# My-VONE-6502_Hex_Display_8_Data_16_Adres.net
KiCad netlist of a schematic drawn in EasyEDA
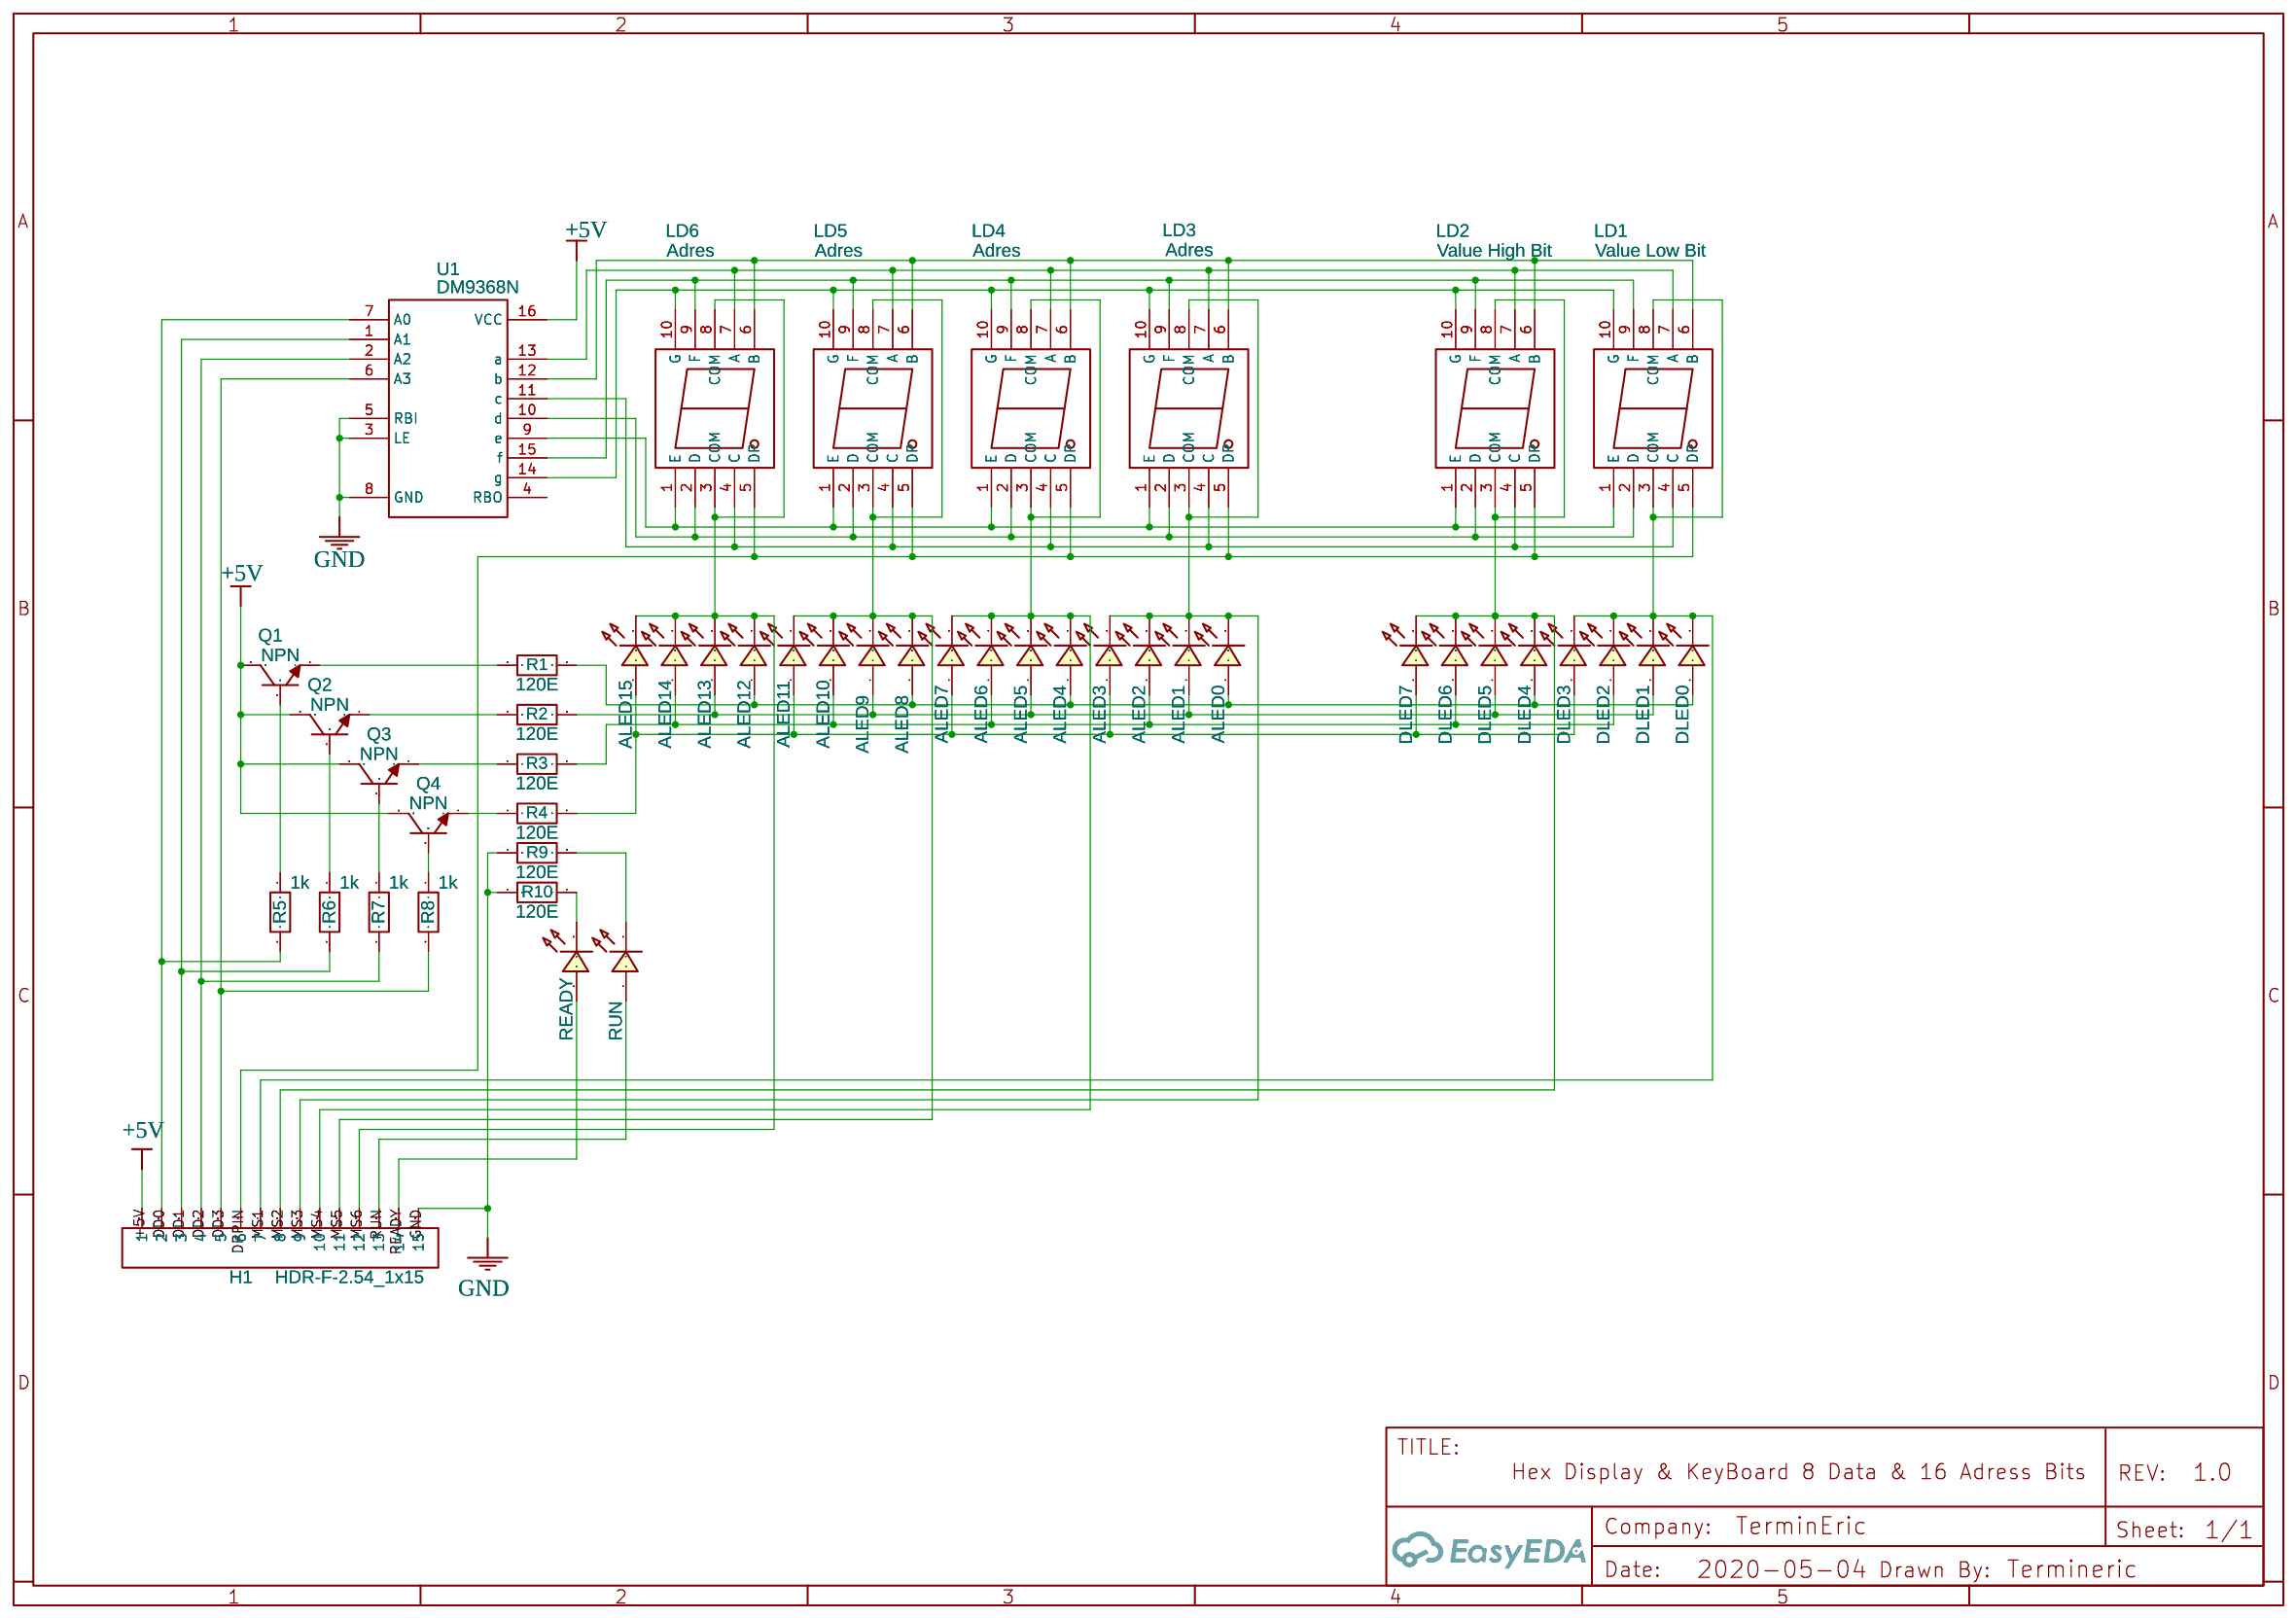
[diagram p0: schematic sheet]

(export (version "E")
  (design (tool "Eeschema 10.0.6"))
  (components
    (comp (ref "ALED0") (value "A0") (libsource (lib "") (part "LED-0603_R")))
    (comp (ref "ALED1") (value "A1") (libsource (lib "") (part "LED-0603_R")))
    (comp (ref "ALED2") (value "A2") (libsource (lib "") (part "LED-0603_R")))
    (comp (ref "ALED3") (value "A3") (libsource (lib "") (part "LED-0603_R")))
    (comp (ref "ALED4") (value "A4") (libsource (lib "") (part "LED-0603_R")))
    (comp (ref "ALED5") (value "A5") (libsource (lib "") (part "LED-0603_R")))
    (comp (ref "ALED6") (value "A6") (libsource (lib "") (part "LED-0603_R")))
    (comp (ref "ALED7") (value "A7") (libsource (lib "") (part "LED-0603_R")))
    (comp (ref "ALED8") (value "A8") (libsource (lib "") (part "LED-0603_R")))
    (comp (ref "ALED9") (value "A9") (libsource (lib "") (part "LED-0603_R")))
    (comp (ref "ALED10") (value "A10") (libsource (lib "") (part "LED-0603_R")))
    (comp (ref "ALED11") (value "A11") (libsource (lib "") (part "LED-0603_R")))
    (comp (ref "ALED12") (value "A12") (libsource (lib "") (part "LED-0603_R")))
    (comp (ref "ALED13") (value "A13") (libsource (lib "") (part "LED-0603_R")))
    (comp (ref "ALED14") (value "A14") (libsource (lib "") (part "LED-0603_R")))
    (comp (ref "ALED15") (value "A15") (libsource (lib "") (part "LED-0603_R")))
    (comp (ref "DLED0") (value "D0") (libsource (lib "") (part "LED-0603_R_1")))
    (comp (ref "DLED1") (value "D1") (libsource (lib "") (part "LED-0603_R_1")))
    (comp (ref "DLED2") (value "D2") (libsource (lib "") (part "LED-0603_R_1")))
    (comp (ref "DLED3") (value "D3") (libsource (lib "") (part "LED-0603_R_1")))
    (comp (ref "DLED4") (value "D4") (libsource (lib "") (part "LED-0603_R_1")))
    (comp (ref "DLED5") (value "D5") (libsource (lib "") (part "LED-0603_R_1")))
    (comp (ref "DLED6") (value "D6") (libsource (lib "") (part "LED-0603_R_1")))
    (comp (ref "DLED7") (value "D7") (libsource (lib "") (part "LED-0603_R_1")))
    (comp (ref "H1")
      (value "HDR-F-2.54_1x15")
      (fields (field (name "BOM_Supplier Part") "C124408"))
      (libsource (lib "") (part "HDR-F-2.54_1x15"))
    )
    (comp (ref "LD1")
      (value "Value Low Bit")
      (fields
        (field (name "BOM_Manufacturer Part") "SLR0561DBA1BD")
        (field (name "BOM_Supplier Part") "C225938")
      )
      (libsource (lib "") (part "Unknown_815_-610"))
    )
    (comp (ref "LD2")
      (value "Value High Bit")
      (fields
        (field (name "BOM_Manufacturer Part") "SLR0561DBA1BD")
        (field (name "BOM_Supplier Part") "C225938")
      )
      (libsource (lib "") (part "Unknown_735_-610"))
    )
    (comp (ref "LD3")
      (value "Adres")
      (fields
        (field (name "BOM_Manufacturer Part") "SLR0561DBA1BD")
        (field (name "BOM_Supplier Part") "SC 52-11 RT")
      )
      (libsource (lib "") (part "Unknown_580_-610"))
    )
    (comp (ref "LD4")
      (value "Adres")
      (fields
        (field (name "BOM_Manufacturer Part") "SLR0561DBA1BD")
        (field (name "BOM_Supplier Part") "C225938")
      )
      (libsource (lib "") (part "Unknown_500_-610"))
    )
    (comp (ref "LD5")
      (value "Adres")
      (fields
        (field (name "BOM_Manufacturer Part") "SLR0561DBA1BD")
        (field (name "BOM_Supplier Part") "C225938")
      )
      (libsource (lib "") (part "Unknown_420_-610"))
    )
    (comp (ref "LD6")
      (value "Adres")
      (fields
        (field (name "BOM_Manufacturer Part") "SLR0561DBA1BD")
        (field (name "BOM_Supplier Part") "C225938")
      )
      (libsource (lib "") (part "Unknown_340_-610"))
    )
    (comp (ref "Q1")
      (value "NPN")
      (fields (field (name "BOM_Manufacturer Part") "2N3904") (field (name "BOM_Supplier Part") "C118538"))
      (libsource (lib "") (part "Unknown_120_-470"))
    )
    (comp (ref "Q2")
      (value "NPN")
      (fields (field (name "BOM_Manufacturer Part") "2N3904") (field (name "BOM_Supplier Part") "C118538"))
      (libsource (lib "") (part "Unknown_145_-445"))
    )
    (comp (ref "Q3")
      (value "NPN")
      (fields (field (name "BOM_Manufacturer Part") "2N3904") (field (name "BOM_Supplier Part") "C118538"))
      (libsource (lib "") (part "Unknown_170_-420"))
    )
    (comp (ref "Q4")
      (value "NPN")
      (fields (field (name "BOM_Manufacturer Part") "2N3904") (field (name "BOM_Supplier Part") "C118538"))
      (libsource (lib "") (part "Unknown_195_-395"))
    )
    (comp (ref "R1") (value "120E") (libsource (lib "") (part "R_0201_EU")))
    (comp (ref "R2") (value "120E") (libsource (lib "") (part "R_0201_EU")))
    (comp (ref "R3") (value "120E") (libsource (lib "") (part "R_0201_EU")))
    (comp (ref "R4") (value "120E") (libsource (lib "") (part "R_0201_EU")))
    (comp (ref "R5") (value "1k") (libsource (lib "") (part "Res_AXIAL-0.3(1/8W)_EU")))
    (comp (ref "R6") (value "1k") (libsource (lib "") (part "Res_AXIAL-0.3(1/8W)_EU")))
    (comp (ref "R7") (value "1k") (libsource (lib "") (part "Res_AXIAL-0.3(1/8W)_EU")))
    (comp (ref "R8") (value "1k") (libsource (lib "") (part "Res_AXIAL-0.3(1/8W)_EU")))
    (comp (ref "R9") (value "120E") (libsource (lib "") (part "R_0201_EU")))
    (comp (ref "R10") (value "120E") (libsource (lib "") (part "R_0201_EU")))
    (comp (ref "READY") (value "A15") (libsource (lib "") (part "LED-0603_R_2")))
    (comp (ref "RUN") (value "A15") (libsource (lib "") (part "LED-0603_R_3")))
    (comp (ref "U1") (value "DM9368N") (libsource (lib "") (part "DM9368N")))
  )
  (nets
    (net (code "1") (name "+5V") (class "Default")
      (node (ref "H1") (pin "1") (pinfunction "1_1") (pintype "unspecified"))
      (node (ref "Q1") (pin "3") (pinfunction "C_3") (pintype "unspecified"))
      (node (ref "Q2") (pin "3") (pinfunction "C_3") (pintype "unspecified"))
      (node (ref "Q3") (pin "3") (pinfunction "C_3") (pintype "unspecified"))
      (node (ref "Q4") (pin "3") (pinfunction "C_3") (pintype "unspecified"))
      (node (ref "U1") (pin "16") (pinfunction "VCC_16") (pintype "passive"))
    )
    (net (code "2") (name "/DD0") (class "Default")
      (node (ref "H1") (pin "2") (pinfunction "2_2") (pintype "unspecified"))
      (node (ref "R5") (pin "2") (pinfunction "2_2") (pintype "unspecified"))
      (node (ref "U1") (pin "7") (pinfunction "A0_7") (pintype "unspecified"))
    )
    (net (code "3") (name "/DD1") (class "Default")
      (node (ref "H1") (pin "3") (pinfunction "3_3") (pintype "unspecified"))
      (node (ref "R6") (pin "2") (pinfunction "2_2") (pintype "unspecified"))
      (node (ref "U1") (pin "1") (pinfunction "A1_1") (pintype "unspecified"))
    )
    (net (code "4") (name "/DD2") (class "Default")
      (node (ref "H1") (pin "4") (pinfunction "4_4") (pintype "unspecified"))
      (node (ref "R7") (pin "2") (pinfunction "2_2") (pintype "unspecified"))
      (node (ref "U1") (pin "2") (pinfunction "A2_2") (pintype "unspecified"))
    )
    (net (code "5") (name "/DD3") (class "Default")
      (node (ref "H1") (pin "5") (pinfunction "5_5") (pintype "unspecified"))
      (node (ref "R8") (pin "2") (pinfunction "2_2") (pintype "unspecified"))
      (node (ref "U1") (pin "6") (pinfunction "A3_6") (pintype "unspecified"))
    )
    (net (code "6") (name "/DPPIN") (class "Default")
      (node (ref "H1") (pin "6") (pinfunction "6_6") (pintype "unspecified"))
      (node (ref "LD1") (pin "5") (pinfunction "DP_5") (pintype "unspecified"))
      (node (ref "LD2") (pin "5") (pinfunction "DP_5") (pintype "unspecified"))
      (node (ref "LD3") (pin "5") (pinfunction "DP_5") (pintype "unspecified"))
      (node (ref "LD4") (pin "5") (pinfunction "DP_5") (pintype "unspecified"))
      (node (ref "LD5") (pin "5") (pinfunction "DP_5") (pintype "unspecified"))
      (node (ref "LD6") (pin "5") (pinfunction "DP_5") (pintype "unspecified"))
    )
    (net (code "7") (name "/MS1") (class "Default")
      (node (ref "DLED0") (pin "2") (pinfunction "2_2") (pintype "unspecified"))
      (node (ref "DLED1") (pin "2") (pinfunction "2_2") (pintype "unspecified"))
      (node (ref "DLED2") (pin "2") (pinfunction "2_2") (pintype "unspecified"))
      (node (ref "DLED3") (pin "2") (pinfunction "2_2") (pintype "unspecified"))
      (node (ref "H1") (pin "7") (pinfunction "7_7") (pintype "unspecified"))
      (node (ref "LD1") (pin "3") (pinfunction "COM_3") (pintype "unspecified"))
      (node (ref "LD1") (pin "8") (pinfunction "COM_8") (pintype "unspecified"))
    )
    (net (code "8") (name "/MS2") (class "Default")
      (node (ref "DLED4") (pin "2") (pinfunction "2_2") (pintype "unspecified"))
      (node (ref "DLED5") (pin "2") (pinfunction "2_2") (pintype "unspecified"))
      (node (ref "DLED6") (pin "2") (pinfunction "2_2") (pintype "unspecified"))
      (node (ref "DLED7") (pin "2") (pinfunction "2_2") (pintype "unspecified"))
      (node (ref "H1") (pin "8") (pinfunction "8_8") (pintype "unspecified"))
      (node (ref "LD2") (pin "3") (pinfunction "COM_3") (pintype "unspecified"))
      (node (ref "LD2") (pin "8") (pinfunction "COM_8") (pintype "unspecified"))
    )
    (net (code "9") (name "/MS3") (class "Default")
      (node (ref "ALED0") (pin "2") (pinfunction "2_2") (pintype "unspecified"))
      (node (ref "ALED1") (pin "2") (pinfunction "2_2") (pintype "unspecified"))
      (node (ref "ALED2") (pin "2") (pinfunction "2_2") (pintype "unspecified"))
      (node (ref "ALED3") (pin "2") (pinfunction "2_2") (pintype "unspecified"))
      (node (ref "H1") (pin "9") (pinfunction "9_9") (pintype "unspecified"))
      (node (ref "LD3") (pin "3") (pinfunction "COM_3") (pintype "unspecified"))
      (node (ref "LD3") (pin "8") (pinfunction "COM_8") (pintype "unspecified"))
    )
    (net (code "10") (name "/MS4") (class "Default")
      (node (ref "ALED4") (pin "2") (pinfunction "2_2") (pintype "unspecified"))
      (node (ref "ALED5") (pin "2") (pinfunction "2_2") (pintype "unspecified"))
      (node (ref "ALED6") (pin "2") (pinfunction "2_2") (pintype "unspecified"))
      (node (ref "ALED7") (pin "2") (pinfunction "2_2") (pintype "unspecified"))
      (node (ref "H1") (pin "10") (pinfunction "10_10") (pintype "unspecified"))
      (node (ref "LD4") (pin "3") (pinfunction "COM_3") (pintype "unspecified"))
      (node (ref "LD4") (pin "8") (pinfunction "COM_8") (pintype "unspecified"))
    )
    (net (code "11") (name "/MS5") (class "Default")
      (node (ref "ALED10") (pin "2") (pinfunction "2_2") (pintype "unspecified"))
      (node (ref "ALED11") (pin "2") (pinfunction "2_2") (pintype "unspecified"))
      (node (ref "ALED8") (pin "2") (pinfunction "2_2") (pintype "unspecified"))
      (node (ref "ALED9") (pin "2") (pinfunction "2_2") (pintype "unspecified"))
      (node (ref "H1") (pin "11") (pinfunction "11_11") (pintype "unspecified"))
      (node (ref "LD5") (pin "3") (pinfunction "COM_3") (pintype "unspecified"))
      (node (ref "LD5") (pin "8") (pinfunction "COM_8") (pintype "unspecified"))
    )
    (net (code "12") (name "/MS6") (class "Default")
      (node (ref "ALED12") (pin "2") (pinfunction "2_2") (pintype "unspecified"))
      (node (ref "ALED13") (pin "2") (pinfunction "2_2") (pintype "unspecified"))
      (node (ref "ALED14") (pin "2") (pinfunction "2_2") (pintype "unspecified"))
      (node (ref "ALED15") (pin "2") (pinfunction "2_2") (pintype "unspecified"))
      (node (ref "H1") (pin "12") (pinfunction "12_12") (pintype "unspecified"))
      (node (ref "LD6") (pin "3") (pinfunction "COM_3") (pintype "unspecified"))
      (node (ref "LD6") (pin "8") (pinfunction "COM_8") (pintype "unspecified"))
    )
    (net (code "13") (name "/READY") (class "Default")
      (node (ref "H1") (pin "14") (pinfunction "14_14") (pintype "unspecified"))
      (node (ref "READY") (pin "1") (pinfunction "1_1") (pintype "unspecified"))
    )
    (net (code "14") (name "/RUN") (class "Default")
      (node (ref "H1") (pin "13") (pinfunction "13_13") (pintype "unspecified"))
      (node (ref "RUN") (pin "1") (pinfunction "1_1") (pintype "unspecified"))
    )
    (net (code "15") (name "GND") (class "Default")
      (node (ref "H1") (pin "15") (pinfunction "15_15") (pintype "unspecified"))
      (node (ref "R10") (pin "1") (pinfunction "1_1") (pintype "unspecified"))
      (node (ref "R9") (pin "1") (pinfunction "1_1") (pintype "unspecified"))
      (node (ref "U1") (pin "3") (pinfunction "LE_3") (pintype "unspecified"))
      (node (ref "U1") (pin "5") (pinfunction "RBI_5") (pintype "unspecified"))
      (node (ref "U1") (pin "8") (pinfunction "GND_8") (pintype "passive"))
    )
    (net (code "16") (name "Net-(ALED0-Pad1)") (class "Default")
      (node (ref "ALED0") (pin "1") (pinfunction "1_1") (pintype "unspecified"))
      (node (ref "ALED12") (pin "1") (pinfunction "1_1") (pintype "unspecified"))
      (node (ref "ALED4") (pin "1") (pinfunction "1_1") (pintype "unspecified"))
      (node (ref "ALED8") (pin "1") (pinfunction "1_1") (pintype "unspecified"))
      (node (ref "DLED0") (pin "1") (pinfunction "1_1") (pintype "unspecified"))
      (node (ref "DLED4") (pin "1") (pinfunction "1_1") (pintype "unspecified"))
      (node (ref "R1") (pin "2") (pinfunction "2_2") (pintype "unspecified"))
    )
    (net (code "17") (name "Net-(ALED1-Pad1)") (class "Default")
      (node (ref "ALED1") (pin "1") (pinfunction "1_1") (pintype "unspecified"))
      (node (ref "ALED13") (pin "1") (pinfunction "1_1") (pintype "unspecified"))
      (node (ref "ALED5") (pin "1") (pinfunction "1_1") (pintype "unspecified"))
      (node (ref "ALED9") (pin "1") (pinfunction "1_1") (pintype "unspecified"))
      (node (ref "DLED1") (pin "1") (pinfunction "1_1") (pintype "unspecified"))
      (node (ref "DLED5") (pin "1") (pinfunction "1_1") (pintype "unspecified"))
      (node (ref "R2") (pin "2") (pinfunction "2_2") (pintype "unspecified"))
    )
    (net (code "18") (name "Net-(ALED10-Pad1)") (class "Default")
      (node (ref "ALED10") (pin "1") (pinfunction "1_1") (pintype "unspecified"))
      (node (ref "ALED14") (pin "1") (pinfunction "1_1") (pintype "unspecified"))
      (node (ref "ALED2") (pin "1") (pinfunction "1_1") (pintype "unspecified"))
      (node (ref "ALED6") (pin "1") (pinfunction "1_1") (pintype "unspecified"))
      (node (ref "DLED2") (pin "1") (pinfunction "1_1") (pintype "unspecified"))
      (node (ref "DLED6") (pin "1") (pinfunction "1_1") (pintype "unspecified"))
      (node (ref "R3") (pin "2") (pinfunction "2_2") (pintype "unspecified"))
    )
    (net (code "19") (name "Net-(ALED11-Pad1)") (class "Default")
      (node (ref "ALED11") (pin "1") (pinfunction "1_1") (pintype "unspecified"))
      (node (ref "ALED15") (pin "1") (pinfunction "1_1") (pintype "unspecified"))
      (node (ref "ALED3") (pin "1") (pinfunction "1_1") (pintype "unspecified"))
      (node (ref "ALED7") (pin "1") (pinfunction "1_1") (pintype "unspecified"))
      (node (ref "DLED3") (pin "1") (pinfunction "1_1") (pintype "unspecified"))
      (node (ref "DLED7") (pin "1") (pinfunction "1_1") (pintype "unspecified"))
      (node (ref "R4") (pin "2") (pinfunction "2_2") (pintype "unspecified"))
    )
    (net (code "20") (name "Net-(LD1-A)") (class "Default")
      (node (ref "LD1") (pin "7") (pinfunction "A_7") (pintype "unspecified"))
      (node (ref "LD2") (pin "7") (pinfunction "A_7") (pintype "unspecified"))
      (node (ref "LD3") (pin "7") (pinfunction "A_7") (pintype "unspecified"))
      (node (ref "LD4") (pin "7") (pinfunction "A_7") (pintype "unspecified"))
      (node (ref "LD5") (pin "7") (pinfunction "A_7") (pintype "unspecified"))
      (node (ref "LD6") (pin "7") (pinfunction "A_7") (pintype "unspecified"))
      (node (ref "U1") (pin "13") (pinfunction "a_13") (pintype "output"))
    )
    (net (code "21") (name "Net-(LD1-B)") (class "Default")
      (node (ref "LD1") (pin "6") (pinfunction "B_6") (pintype "unspecified"))
      (node (ref "LD2") (pin "6") (pinfunction "B_6") (pintype "unspecified"))
      (node (ref "LD3") (pin "6") (pinfunction "B_6") (pintype "unspecified"))
      (node (ref "LD4") (pin "6") (pinfunction "B_6") (pintype "unspecified"))
      (node (ref "LD5") (pin "6") (pinfunction "B_6") (pintype "unspecified"))
      (node (ref "LD6") (pin "6") (pinfunction "B_6") (pintype "unspecified"))
      (node (ref "U1") (pin "12") (pinfunction "b_12") (pintype "output"))
    )
    (net (code "22") (name "Net-(LD1-C)") (class "Default")
      (node (ref "LD1") (pin "4") (pinfunction "C_4") (pintype "unspecified"))
      (node (ref "LD2") (pin "4") (pinfunction "C_4") (pintype "unspecified"))
      (node (ref "LD3") (pin "4") (pinfunction "C_4") (pintype "unspecified"))
      (node (ref "LD4") (pin "4") (pinfunction "C_4") (pintype "unspecified"))
      (node (ref "LD5") (pin "4") (pinfunction "C_4") (pintype "unspecified"))
      (node (ref "LD6") (pin "4") (pinfunction "C_4") (pintype "unspecified"))
      (node (ref "U1") (pin "11") (pinfunction "c_11") (pintype "output"))
    )
    (net (code "23") (name "Net-(LD1-D)") (class "Default")
      (node (ref "LD1") (pin "2") (pinfunction "D_2") (pintype "unspecified"))
      (node (ref "LD2") (pin "2") (pinfunction "D_2") (pintype "unspecified"))
      (node (ref "LD3") (pin "2") (pinfunction "D_2") (pintype "unspecified"))
      (node (ref "LD4") (pin "2") (pinfunction "D_2") (pintype "unspecified"))
      (node (ref "LD5") (pin "2") (pinfunction "D_2") (pintype "unspecified"))
      (node (ref "LD6") (pin "2") (pinfunction "D_2") (pintype "unspecified"))
      (node (ref "U1") (pin "10") (pinfunction "d_10") (pintype "output"))
    )
    (net (code "24") (name "Net-(LD1-E)") (class "Default")
      (node (ref "LD1") (pin "1") (pinfunction "E_1") (pintype "unspecified"))
      (node (ref "LD2") (pin "1") (pinfunction "E_1") (pintype "unspecified"))
      (node (ref "LD3") (pin "1") (pinfunction "E_1") (pintype "unspecified"))
      (node (ref "LD4") (pin "1") (pinfunction "E_1") (pintype "unspecified"))
      (node (ref "LD5") (pin "1") (pinfunction "E_1") (pintype "unspecified"))
      (node (ref "LD6") (pin "1") (pinfunction "E_1") (pintype "unspecified"))
      (node (ref "U1") (pin "9") (pinfunction "e_9") (pintype "output"))
    )
    (net (code "25") (name "Net-(LD1-F)") (class "Default")
      (node (ref "LD1") (pin "9") (pinfunction "F_9") (pintype "unspecified"))
      (node (ref "LD2") (pin "9") (pinfunction "F_9") (pintype "unspecified"))
      (node (ref "LD3") (pin "9") (pinfunction "F_9") (pintype "unspecified"))
      (node (ref "LD4") (pin "9") (pinfunction "F_9") (pintype "unspecified"))
      (node (ref "LD5") (pin "9") (pinfunction "F_9") (pintype "unspecified"))
      (node (ref "LD6") (pin "9") (pinfunction "F_9") (pintype "unspecified"))
      (node (ref "U1") (pin "15") (pinfunction "f_15") (pintype "output"))
    )
    (net (code "26") (name "Net-(LD1-G)") (class "Default")
      (node (ref "LD1") (pin "10") (pinfunction "G_10") (pintype "unspecified"))
      (node (ref "LD2") (pin "10") (pinfunction "G_10") (pintype "unspecified"))
      (node (ref "LD3") (pin "10") (pinfunction "G_10") (pintype "unspecified"))
      (node (ref "LD4") (pin "10") (pinfunction "G_10") (pintype "unspecified"))
      (node (ref "LD5") (pin "10") (pinfunction "G_10") (pintype "unspecified"))
      (node (ref "LD6") (pin "10") (pinfunction "G_10") (pintype "unspecified"))
      (node (ref "U1") (pin "14") (pinfunction "g_14") (pintype "output"))
    )
    (net (code "27") (name "Net-(Q1-B)") (class "Default")
      (node (ref "Q1") (pin "2") (pinfunction "B_2") (pintype "unspecified"))
      (node (ref "R5") (pin "1") (pinfunction "1_1") (pintype "unspecified"))
    )
    (net (code "28") (name "Net-(Q1-E)") (class "Default")
      (node (ref "Q1") (pin "1") (pinfunction "E_1") (pintype "unspecified"))
      (node (ref "R1") (pin "1") (pinfunction "1_1") (pintype "unspecified"))
    )
    (net (code "29") (name "Net-(Q2-B)") (class "Default")
      (node (ref "Q2") (pin "2") (pinfunction "B_2") (pintype "unspecified"))
      (node (ref "R6") (pin "1") (pinfunction "1_1") (pintype "unspecified"))
    )
    (net (code "30") (name "Net-(Q2-E)") (class "Default")
      (node (ref "Q2") (pin "1") (pinfunction "E_1") (pintype "unspecified"))
      (node (ref "R2") (pin "1") (pinfunction "1_1") (pintype "unspecified"))
    )
    (net (code "31") (name "Net-(Q3-B)") (class "Default")
      (node (ref "Q3") (pin "2") (pinfunction "B_2") (pintype "unspecified"))
      (node (ref "R7") (pin "1") (pinfunction "1_1") (pintype "unspecified"))
    )
    (net (code "32") (name "Net-(Q3-E)") (class "Default")
      (node (ref "Q3") (pin "1") (pinfunction "E_1") (pintype "unspecified"))
      (node (ref "R3") (pin "1") (pinfunction "1_1") (pintype "unspecified"))
    )
    (net (code "33") (name "Net-(Q4-B)") (class "Default")
      (node (ref "Q4") (pin "2") (pinfunction "B_2") (pintype "unspecified"))
      (node (ref "R8") (pin "1") (pinfunction "1_1") (pintype "unspecified"))
    )
    (net (code "34") (name "Net-(Q4-E)") (class "Default")
      (node (ref "Q4") (pin "1") (pinfunction "E_1") (pintype "unspecified"))
      (node (ref "R4") (pin "1") (pinfunction "1_1") (pintype "unspecified"))
    )
    (net (code "35") (name "Net-(R9-Pad2)") (class "Default")
      (node (ref "R9") (pin "2") (pinfunction "2_2") (pintype "unspecified"))
      (node (ref "RUN") (pin "2") (pinfunction "2_2") (pintype "unspecified"))
    )
    (net (code "36") (name "Net-(R10-Pad2)") (class "Default")
      (node (ref "R10") (pin "2") (pinfunction "2_2") (pintype "unspecified"))
      (node (ref "READY") (pin "2") (pinfunction "2_2") (pintype "unspecified"))
    )
    (net (code "37") (name "unconnected-(U1-RBO-Pad4)") (class "Default")
      (node (ref "U1") (pin "4") (pinfunction "RBO_4") (pintype "bidirectional"))
    )
  )
)
